# decade_pwm_rgb_led.net
KiCad netlist of a schematic drawn in EAGLE
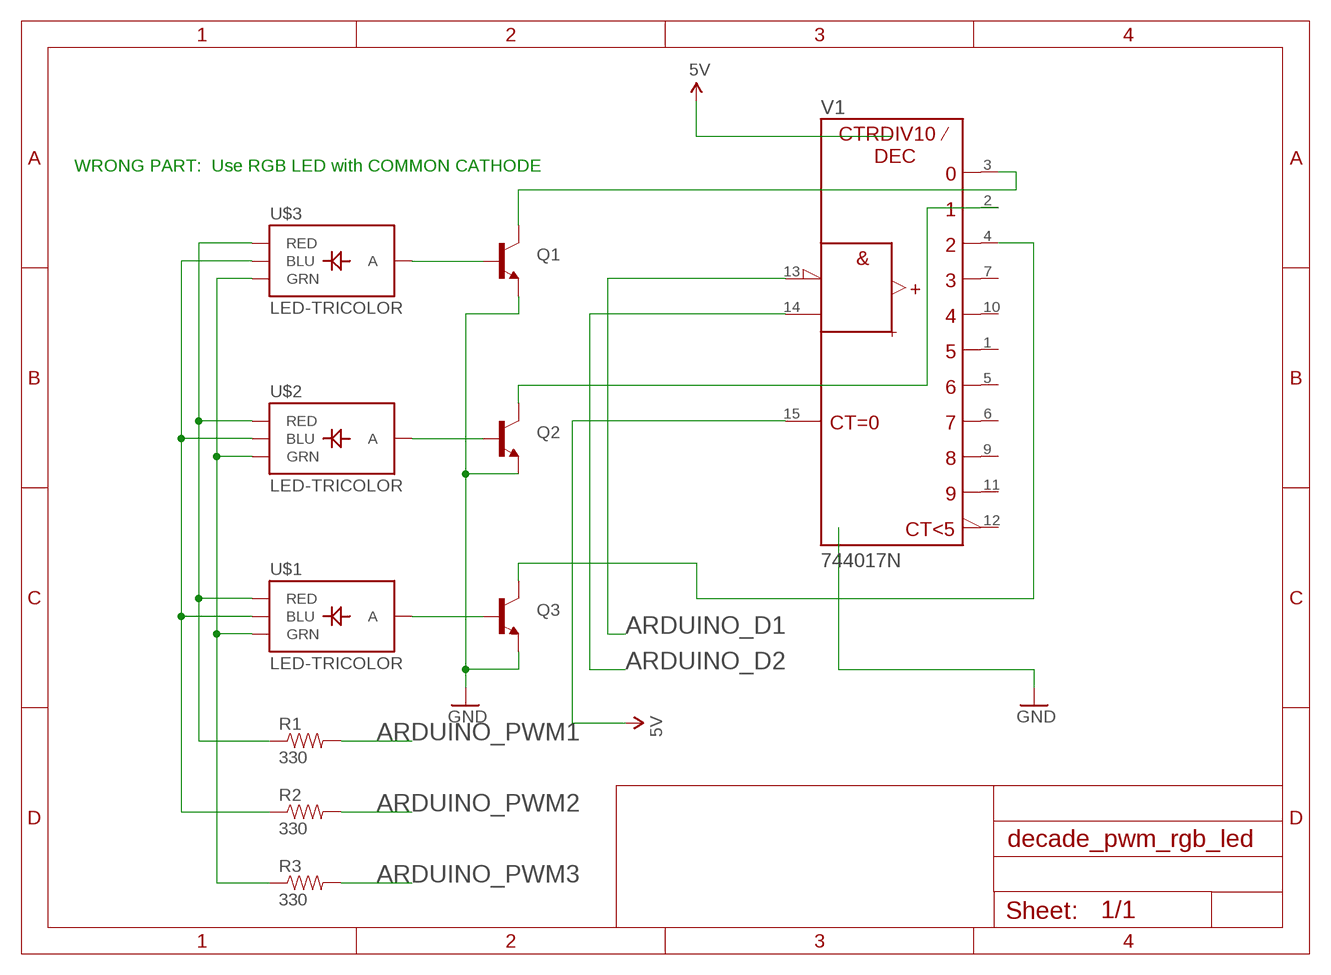
[diagram p0: schematic, sheet 1]

(export (version "E")
  (design (tool "Eeschema 10.0.6"))
  (components
    (comp (ref "Q1")
      (value "TRANSISTOR_NPNTO-92-AMMO")
      (footprint "eagle-import:TO-92-AMMO")
      (libsource (lib "eagle-import") (part "TRANSISTOR_NPNTO-92-AMMO"))
    )
    (comp (ref "Q2")
      (value "TRANSISTOR_NPNTO-92-AMMO")
      (footprint "eagle-import:TO-92-AMMO")
      (libsource (lib "eagle-import") (part "TRANSISTOR_NPNTO-92-AMMO"))
    )
    (comp (ref "Q3")
      (value "TRANSISTOR_NPNTO-92-AMMO")
      (footprint "eagle-import:TO-92-AMMO")
      (libsource (lib "eagle-import") (part "TRANSISTOR_NPNTO-92-AMMO"))
    )
    (comp (ref "R1")
      (value "330")
      (footprint "eagle-import:AXIAL-0.4")
      (libsource (lib "eagle-import") (part "RESISTORPTH-1/4W"))
    )
    (comp (ref "R2")
      (value "330")
      (footprint "eagle-import:AXIAL-0.4")
      (libsource (lib "eagle-import") (part "RESISTORPTH-1/4W"))
    )
    (comp (ref "R3")
      (value "330")
      (footprint "eagle-import:AXIAL-0.4")
      (libsource (lib "eagle-import") (part "RESISTORPTH-1/4W"))
    )
    (comp (ref "U$1")
      (value "LED-TRICOLOR")
      (footprint "eagle-import:LED-TRICOLOR-SMD")
      (libsource (lib "eagle-import") (part "LED-TRICOLOR"))
    )
    (comp (ref "U$2")
      (value "LED-TRICOLOR")
      (footprint "eagle-import:LED-TRICOLOR-SMD")
      (libsource (lib "eagle-import") (part "LED-TRICOLOR"))
    )
    (comp (ref "U$3")
      (value "LED-TRICOLOR")
      (footprint "eagle-import:LED-TRICOLOR-SMD")
      (libsource (lib "eagle-import") (part "LED-TRICOLOR"))
    )
    (comp (ref "V1")
      (value "744017N")
      (footprint "eagle-import:DIL16")
      (libsource (lib "eagle-import") (part "744017N"))
    )
  )
  (nets
    (net (code "1") (name "/ARDUINO_D1") (class "Default")
      (node (ref "V1") (pin "13") (pinfunction "~{CLKEN}_13") (pintype "input"))
    )
    (net (code "2") (name "/ARDUINO_D2") (class "Default")
      (node (ref "V1") (pin "14") (pinfunction "CLK_14") (pintype "input"))
    )
    (net (code "3") (name "/ARDUINO_PWM1") (class "Default")
      (node (ref "R1") (pin "P$2") (pinfunction "2_P$2") (pintype "passive"))
    )
    (net (code "4") (name "/ARDUINO_PWM2") (class "Default")
      (node (ref "R2") (pin "P$2") (pinfunction "2_P$2") (pintype "passive"))
    )
    (net (code "5") (name "/ARDUINO_PWM3") (class "Default")
      (node (ref "R3") (pin "P$2") (pinfunction "2_P$2") (pintype "passive"))
    )
    (net (code "6") (name "5V") (class "Default")
      (node (ref "V1") (pin "15") (pinfunction "CLR_15") (pintype "input"))
    )
    (net (code "7") (name "GND") (class "Default")
      (node (ref "Q1") (pin "1") (pinfunction "E_1") (pintype "passive"))
      (node (ref "Q2") (pin "1") (pinfunction "E_1") (pintype "passive"))
      (node (ref "Q3") (pin "1") (pinfunction "E_1") (pintype "passive"))
    )
    (net (code "8") (name "Net-(Q1-B)") (class "Default")
      (node (ref "Q1") (pin "2") (pinfunction "B_2") (pintype "passive"))
      (node (ref "U$3") (pin "A") (pinfunction "A_A") (pintype "bidirectional"))
    )
    (net (code "9") (name "Net-(Q1-C)") (class "Default")
      (node (ref "Q1") (pin "3") (pinfunction "C_3") (pintype "passive"))
      (node (ref "V1") (pin "3") (pinfunction "Y0_3") (pintype "output"))
    )
    (net (code "10") (name "Net-(Q2-B)") (class "Default")
      (node (ref "Q2") (pin "2") (pinfunction "B_2") (pintype "passive"))
      (node (ref "U$2") (pin "A") (pinfunction "A_A") (pintype "bidirectional"))
    )
    (net (code "11") (name "Net-(Q2-C)") (class "Default")
      (node (ref "Q2") (pin "3") (pinfunction "C_3") (pintype "passive"))
      (node (ref "V1") (pin "2") (pinfunction "Y1_2") (pintype "output"))
    )
    (net (code "12") (name "Net-(Q3-B)") (class "Default")
      (node (ref "Q3") (pin "2") (pinfunction "B_2") (pintype "passive"))
      (node (ref "U$1") (pin "A") (pinfunction "A_A") (pintype "bidirectional"))
    )
    (net (code "13") (name "Net-(Q3-C)") (class "Default")
      (node (ref "Q3") (pin "3") (pinfunction "C_3") (pintype "passive"))
      (node (ref "V1") (pin "4") (pinfunction "Y2_4") (pintype "output"))
    )
    (net (code "14") (name "Net-(R1-1)") (class "Default")
      (node (ref "R1") (pin "P$1") (pinfunction "1_P$1") (pintype "passive"))
      (node (ref "U$1") (pin "R") (pinfunction "RED_R") (pintype "bidirectional"))
      (node (ref "U$2") (pin "R") (pinfunction "RED_R") (pintype "bidirectional"))
      (node (ref "U$3") (pin "R") (pinfunction "RED_R") (pintype "bidirectional"))
    )
    (net (code "15") (name "Net-(R2-1)") (class "Default")
      (node (ref "R2") (pin "P$1") (pinfunction "1_P$1") (pintype "passive"))
      (node (ref "U$1") (pin "B") (pinfunction "BLU_B") (pintype "bidirectional"))
      (node (ref "U$2") (pin "B") (pinfunction "BLU_B") (pintype "bidirectional"))
      (node (ref "U$3") (pin "B") (pinfunction "BLU_B") (pintype "bidirectional"))
    )
    (net (code "16") (name "Net-(R3-1)") (class "Default")
      (node (ref "R3") (pin "P$1") (pinfunction "1_P$1") (pintype "passive"))
      (node (ref "U$1") (pin "G") (pinfunction "GRN_G") (pintype "bidirectional"))
      (node (ref "U$2") (pin "G") (pinfunction "GRN_G") (pintype "bidirectional"))
      (node (ref "U$3") (pin "G") (pinfunction "GRN_G") (pintype "bidirectional"))
    )
    (net (code "17") (name "unconnected-(V1C-CO-Pad12)") (class "Default")
      (node (ref "V1") (pin "12") (pinfunction "CO_12") (pintype "output"))
    )
    (net (code "18") (name "unconnected-(V1C-Y3-Pad7)") (class "Default")
      (node (ref "V1") (pin "7") (pinfunction "Y3_7") (pintype "output"))
    )
    (net (code "19") (name "unconnected-(V1C-Y4-Pad10)") (class "Default")
      (node (ref "V1") (pin "10") (pinfunction "Y4_10") (pintype "output"))
    )
    (net (code "20") (name "unconnected-(V1C-Y5-Pad1)") (class "Default")
      (node (ref "V1") (pin "1") (pinfunction "Y5_1") (pintype "output"))
    )
    (net (code "21") (name "unconnected-(V1C-Y6-Pad5)") (class "Default")
      (node (ref "V1") (pin "5") (pinfunction "Y6_5") (pintype "output"))
    )
    (net (code "22") (name "unconnected-(V1C-Y7-Pad6)") (class "Default")
      (node (ref "V1") (pin "6") (pinfunction "Y7_6") (pintype "output"))
    )
    (net (code "23") (name "unconnected-(V1C-Y8-Pad9)") (class "Default")
      (node (ref "V1") (pin "9") (pinfunction "Y8_9") (pintype "output"))
    )
    (net (code "24") (name "unconnected-(V1C-Y9-Pad11)") (class "Default")
      (node (ref "V1") (pin "11") (pinfunction "Y9_11") (pintype "output"))
    )
  )
)
